# T4p1_thruhole.net
KiCad netlist of a schematic drawn in EAGLE
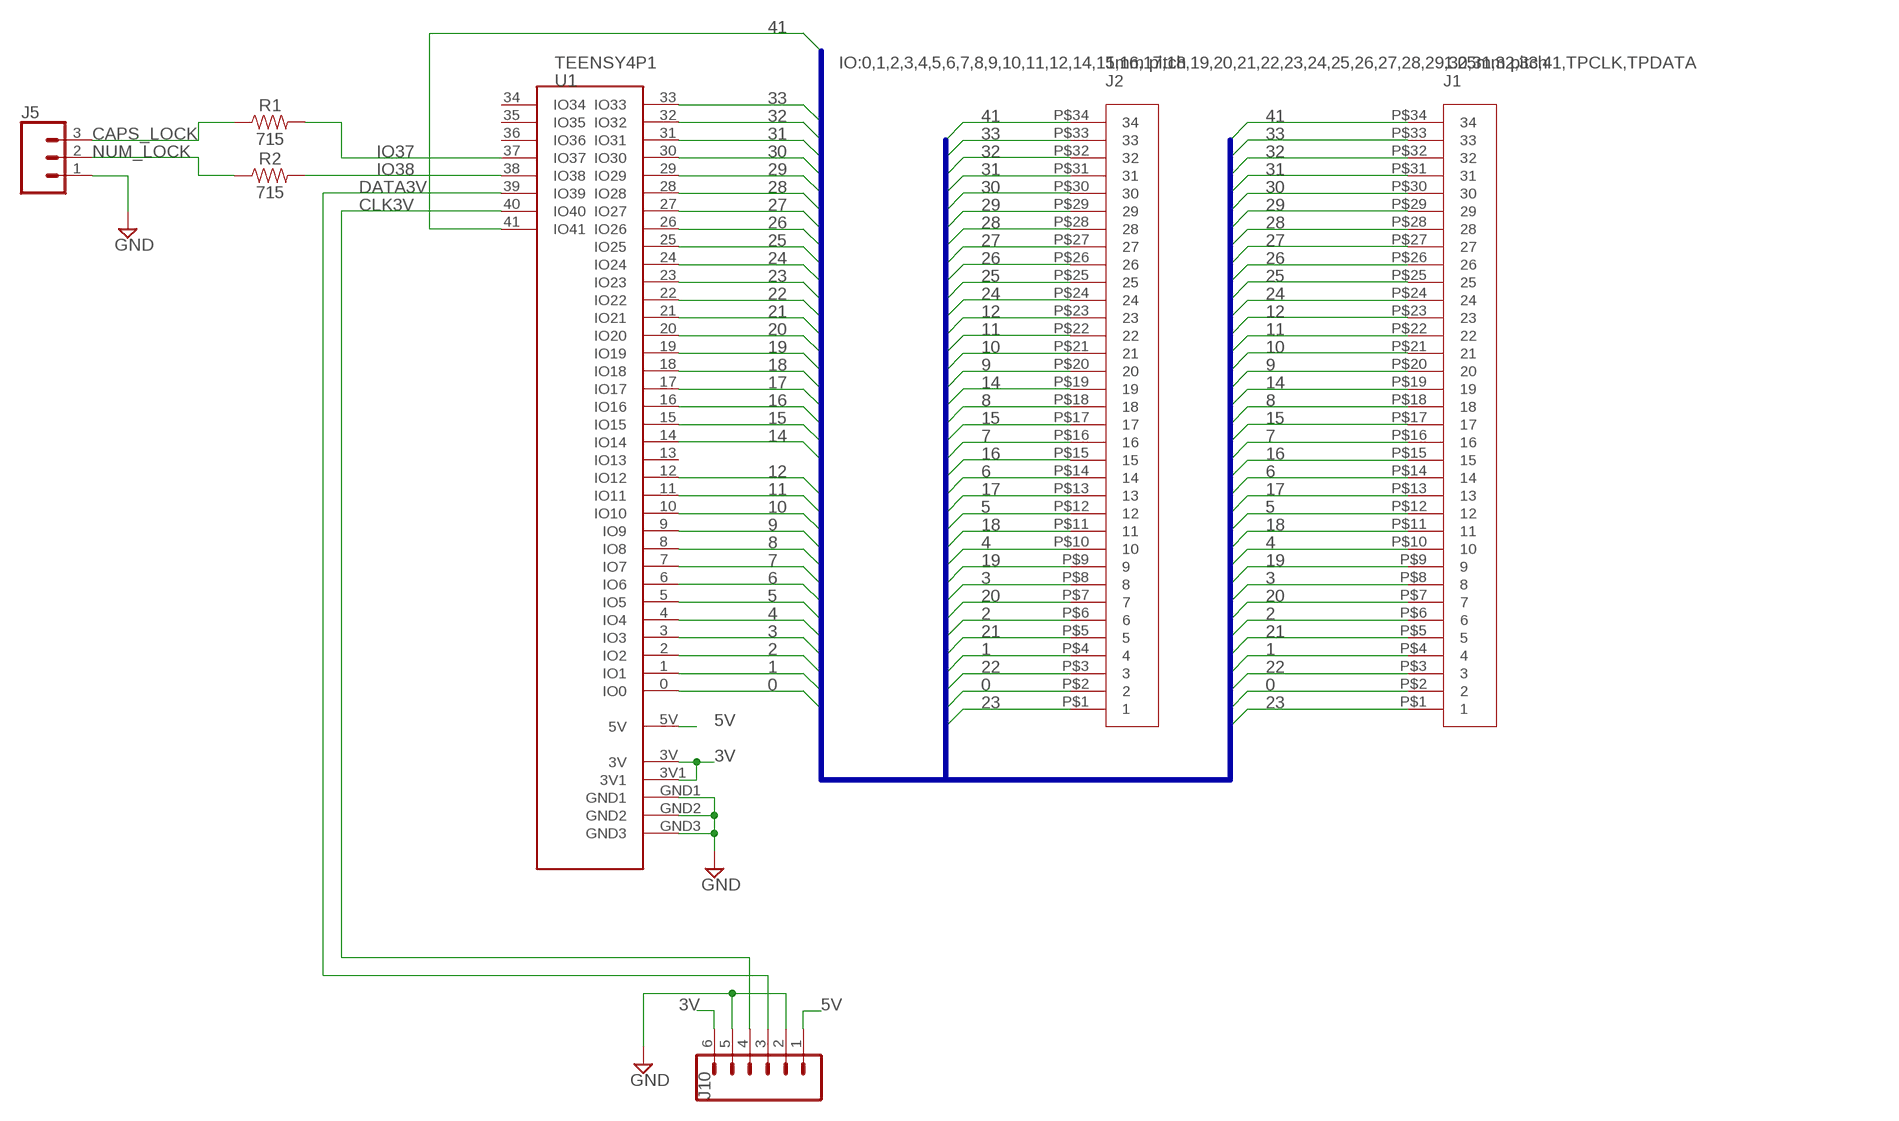
[diagram p0: schematic, sheet 1]

(export (version "E")
  (design (tool "Eeschema 10.0.6"))
  (components
    (comp (ref "J1")
      (value "1P25MM_THRUHOLE")
      (footprint "eagle-import:1P25MM_THRUHOLE")
      (libsource (lib "eagle-import") (part "1P25MM_THRUHOLE"))
    )
    (comp (ref "J2")
      (value "1MM_THRUHOLE")
      (footprint "eagle-import:1MM_THRUHOLE")
      (libsource (lib "eagle-import") (part "1MM_THRUHOLE"))
    )
    (comp (ref "J5")
      (value "CONN_031X03_NO_SILK")
      (footprint "eagle-import:1X03_NO_SILK")
      (libsource (lib "eagle-import") (part "CONN_031X03_NO_SILK"))
    )
    (comp (ref "J10")
      (value "CONN_06NO_SILK_NO_POP")
      (footprint "eagle-import:1X06_NO_SILK")
      (libsource (lib "eagle-import") (part "CONN_06NO_SILK_NO_POP"))
    )
    (comp (ref "R1")
      (value "715")
      (footprint "eagle-import:AXIAL-0.3")
      (libsource (lib "eagle-import") (part "RESISTOR_AXIAL"))
    )
    (comp (ref "R2")
      (value "715")
      (footprint "eagle-import:AXIAL-0.3")
      (libsource (lib "eagle-import") (part "RESISTOR_AXIAL"))
    )
    (comp (ref "U1")
      (value "TEENSY4P1")
      (footprint "eagle-import:TEENSY4P1")
      (libsource (lib "eagle-import") (part "TEENSYP41"))
    )
  )
  (nets
    (net (code "4") (name "/0") (class "Default")
      (node (ref "J1") (pin "P$2") (pinfunction "2_P$2") (pintype "bidirectional"))
      (node (ref "J2") (pin "P$2") (pinfunction "2_P$2") (pintype "bidirectional"))
      (node (ref "U1") (pin "0") (pinfunction "IO0_0") (pintype "bidirectional"))
    )
    (net (code "5") (name "/1") (class "Default")
      (node (ref "J1") (pin "P$4") (pinfunction "4_P$4") (pintype "bidirectional"))
      (node (ref "J2") (pin "P$4") (pinfunction "4_P$4") (pintype "bidirectional"))
      (node (ref "U1") (pin "1") (pinfunction "IO1_1") (pintype "bidirectional"))
    )
    (net (code "6") (name "/2") (class "Default")
      (node (ref "J1") (pin "P$6") (pinfunction "6_P$6") (pintype "bidirectional"))
      (node (ref "J2") (pin "P$6") (pinfunction "6_P$6") (pintype "bidirectional"))
      (node (ref "U1") (pin "2") (pinfunction "IO2_2") (pintype "bidirectional"))
    )
    (net (code "7") (name "/3") (class "Default")
      (node (ref "J1") (pin "P$8") (pinfunction "8_P$8") (pintype "bidirectional"))
      (node (ref "J2") (pin "P$8") (pinfunction "8_P$8") (pintype "bidirectional"))
      (node (ref "U1") (pin "3") (pinfunction "IO3_3") (pintype "bidirectional"))
    )
    (net (code "8") (name "/3V") (class "Default")
      (node (ref "J10") (pin "6") (pinfunction "6_6") (pintype "passive"))
      (node (ref "U1") (pin "3V") (pinfunction "3V_3V") (pintype "bidirectional"))
      (node (ref "U1") (pin "3V1") (pinfunction "3V1_3V1") (pintype "bidirectional"))
    )
    (net (code "9") (name "/4") (class "Default")
      (node (ref "J1") (pin "P$10") (pinfunction "10_P$10") (pintype "bidirectional"))
      (node (ref "J2") (pin "P$10") (pinfunction "10_P$10") (pintype "bidirectional"))
      (node (ref "U1") (pin "4") (pinfunction "IO4_4") (pintype "bidirectional"))
    )
    (net (code "10") (name "/5") (class "Default")
      (node (ref "J1") (pin "P$12") (pinfunction "12_P$12") (pintype "bidirectional"))
      (node (ref "J2") (pin "P$12") (pinfunction "12_P$12") (pintype "bidirectional"))
      (node (ref "U1") (pin "5") (pinfunction "IO5_5") (pintype "bidirectional"))
    )
    (net (code "11") (name "/5V") (class "Default")
      (node (ref "J10") (pin "1") (pinfunction "1_1") (pintype "passive"))
      (node (ref "U1") (pin "5V") (pinfunction "5V_5V") (pintype "bidirectional"))
    )
    (net (code "12") (name "/6") (class "Default")
      (node (ref "J1") (pin "P$14") (pinfunction "14_P$14") (pintype "bidirectional"))
      (node (ref "J2") (pin "P$14") (pinfunction "14_P$14") (pintype "bidirectional"))
      (node (ref "U1") (pin "6") (pinfunction "IO6_6") (pintype "bidirectional"))
    )
    (net (code "13") (name "/7") (class "Default")
      (node (ref "J1") (pin "P$16") (pinfunction "16_P$16") (pintype "bidirectional"))
      (node (ref "J2") (pin "P$16") (pinfunction "16_P$16") (pintype "bidirectional"))
      (node (ref "U1") (pin "7") (pinfunction "IO7_7") (pintype "bidirectional"))
    )
    (net (code "14") (name "/8") (class "Default")
      (node (ref "J1") (pin "P$18") (pinfunction "18_P$18") (pintype "bidirectional"))
      (node (ref "J2") (pin "P$18") (pinfunction "18_P$18") (pintype "bidirectional"))
      (node (ref "U1") (pin "8") (pinfunction "IO8_8") (pintype "bidirectional"))
    )
    (net (code "15") (name "/9") (class "Default")
      (node (ref "J1") (pin "P$20") (pinfunction "20_P$20") (pintype "bidirectional"))
      (node (ref "J2") (pin "P$20") (pinfunction "20_P$20") (pintype "bidirectional"))
      (node (ref "U1") (pin "9") (pinfunction "IO9_9") (pintype "bidirectional"))
    )
    (net (code "16") (name "/10") (class "Default")
      (node (ref "J1") (pin "P$21") (pinfunction "21_P$21") (pintype "bidirectional"))
      (node (ref "J2") (pin "P$21") (pinfunction "21_P$21") (pintype "bidirectional"))
      (node (ref "U1") (pin "10") (pinfunction "IO10_10") (pintype "bidirectional"))
    )
    (net (code "17") (name "/11") (class "Default")
      (node (ref "J1") (pin "P$22") (pinfunction "22_P$22") (pintype "bidirectional"))
      (node (ref "J2") (pin "P$22") (pinfunction "22_P$22") (pintype "bidirectional"))
      (node (ref "U1") (pin "11") (pinfunction "IO11_11") (pintype "bidirectional"))
    )
    (net (code "18") (name "/12") (class "Default")
      (node (ref "J1") (pin "P$23") (pinfunction "23_P$23") (pintype "bidirectional"))
      (node (ref "J2") (pin "P$23") (pinfunction "23_P$23") (pintype "bidirectional"))
      (node (ref "U1") (pin "12") (pinfunction "IO12_12") (pintype "bidirectional"))
    )
    (net (code "19") (name "/14") (class "Default")
      (node (ref "J1") (pin "P$19") (pinfunction "19_P$19") (pintype "bidirectional"))
      (node (ref "J2") (pin "P$19") (pinfunction "19_P$19") (pintype "bidirectional"))
      (node (ref "U1") (pin "14") (pinfunction "IO14_14") (pintype "bidirectional"))
    )
    (net (code "20") (name "/15") (class "Default")
      (node (ref "J1") (pin "P$17") (pinfunction "17_P$17") (pintype "bidirectional"))
      (node (ref "J2") (pin "P$17") (pinfunction "17_P$17") (pintype "bidirectional"))
      (node (ref "U1") (pin "15") (pinfunction "IO15_15") (pintype "bidirectional"))
    )
    (net (code "21") (name "/16") (class "Default")
      (node (ref "J1") (pin "P$15") (pinfunction "15_P$15") (pintype "bidirectional"))
      (node (ref "J2") (pin "P$15") (pinfunction "15_P$15") (pintype "bidirectional"))
      (node (ref "U1") (pin "16") (pinfunction "IO16_16") (pintype "bidirectional"))
    )
    (net (code "22") (name "/17") (class "Default")
      (node (ref "J1") (pin "P$13") (pinfunction "13_P$13") (pintype "bidirectional"))
      (node (ref "J2") (pin "P$13") (pinfunction "13_P$13") (pintype "bidirectional"))
      (node (ref "U1") (pin "17") (pinfunction "IO17_17") (pintype "bidirectional"))
    )
    (net (code "23") (name "/18") (class "Default")
      (node (ref "J1") (pin "P$11") (pinfunction "11_P$11") (pintype "bidirectional"))
      (node (ref "J2") (pin "P$11") (pinfunction "11_P$11") (pintype "bidirectional"))
      (node (ref "U1") (pin "18") (pinfunction "IO18_18") (pintype "bidirectional"))
    )
    (net (code "24") (name "/19") (class "Default")
      (node (ref "J1") (pin "P$9") (pinfunction "9_P$9") (pintype "bidirectional"))
      (node (ref "J2") (pin "P$9") (pinfunction "9_P$9") (pintype "bidirectional"))
      (node (ref "U1") (pin "19") (pinfunction "IO19_19") (pintype "bidirectional"))
    )
    (net (code "25") (name "/20") (class "Default")
      (node (ref "J1") (pin "P$7") (pinfunction "7_P$7") (pintype "bidirectional"))
      (node (ref "J2") (pin "P$7") (pinfunction "7_P$7") (pintype "bidirectional"))
      (node (ref "U1") (pin "20") (pinfunction "IO20_20") (pintype "bidirectional"))
    )
    (net (code "26") (name "/21") (class "Default")
      (node (ref "J1") (pin "P$5") (pinfunction "5_P$5") (pintype "bidirectional"))
      (node (ref "J2") (pin "P$5") (pinfunction "5_P$5") (pintype "bidirectional"))
      (node (ref "U1") (pin "21") (pinfunction "IO21_21") (pintype "bidirectional"))
    )
    (net (code "27") (name "/22") (class "Default")
      (node (ref "J1") (pin "P$3") (pinfunction "3_P$3") (pintype "bidirectional"))
      (node (ref "J2") (pin "P$3") (pinfunction "3_P$3") (pintype "bidirectional"))
      (node (ref "U1") (pin "22") (pinfunction "IO22_22") (pintype "bidirectional"))
    )
    (net (code "28") (name "/23") (class "Default")
      (node (ref "J1") (pin "P$1") (pinfunction "1_P$1") (pintype "bidirectional"))
      (node (ref "J2") (pin "P$1") (pinfunction "1_P$1") (pintype "bidirectional"))
      (node (ref "U1") (pin "23") (pinfunction "IO23_23") (pintype "bidirectional"))
    )
    (net (code "29") (name "/24") (class "Default")
      (node (ref "J1") (pin "P$24") (pinfunction "24_P$24") (pintype "bidirectional"))
      (node (ref "J2") (pin "P$24") (pinfunction "24_P$24") (pintype "bidirectional"))
      (node (ref "U1") (pin "24") (pinfunction "IO24_24") (pintype "bidirectional"))
    )
    (net (code "30") (name "/25") (class "Default")
      (node (ref "J1") (pin "P$25") (pinfunction "25_P$25") (pintype "bidirectional"))
      (node (ref "J2") (pin "P$25") (pinfunction "25_P$25") (pintype "bidirectional"))
      (node (ref "U1") (pin "25") (pinfunction "IO25_25") (pintype "bidirectional"))
    )
    (net (code "31") (name "/26") (class "Default")
      (node (ref "J1") (pin "P$26") (pinfunction "26_P$26") (pintype "bidirectional"))
      (node (ref "J2") (pin "P$26") (pinfunction "26_P$26") (pintype "bidirectional"))
      (node (ref "U1") (pin "26") (pinfunction "IO26_26") (pintype "bidirectional"))
    )
    (net (code "32") (name "/27") (class "Default")
      (node (ref "J1") (pin "P$27") (pinfunction "27_P$27") (pintype "bidirectional"))
      (node (ref "J2") (pin "P$27") (pinfunction "27_P$27") (pintype "bidirectional"))
      (node (ref "U1") (pin "27") (pinfunction "IO27_27") (pintype "bidirectional"))
    )
    (net (code "33") (name "/28") (class "Default")
      (node (ref "J1") (pin "P$28") (pinfunction "28_P$28") (pintype "bidirectional"))
      (node (ref "J2") (pin "P$28") (pinfunction "28_P$28") (pintype "bidirectional"))
      (node (ref "U1") (pin "28") (pinfunction "IO28_28") (pintype "bidirectional"))
    )
    (net (code "34") (name "/29") (class "Default")
      (node (ref "J1") (pin "P$29") (pinfunction "29_P$29") (pintype "bidirectional"))
      (node (ref "J2") (pin "P$29") (pinfunction "29_P$29") (pintype "bidirectional"))
      (node (ref "U1") (pin "29") (pinfunction "IO29_29") (pintype "bidirectional"))
    )
    (net (code "35") (name "/30") (class "Default")
      (node (ref "J1") (pin "P$30") (pinfunction "30_P$30") (pintype "bidirectional"))
      (node (ref "J2") (pin "P$30") (pinfunction "30_P$30") (pintype "bidirectional"))
      (node (ref "U1") (pin "30") (pinfunction "IO30_30") (pintype "bidirectional"))
    )
    (net (code "36") (name "/31") (class "Default")
      (node (ref "J1") (pin "P$31") (pinfunction "31_P$31") (pintype "bidirectional"))
      (node (ref "J2") (pin "P$31") (pinfunction "31_P$31") (pintype "bidirectional"))
      (node (ref "U1") (pin "31") (pinfunction "IO31_31") (pintype "bidirectional"))
    )
    (net (code "37") (name "/32") (class "Default")
      (node (ref "J1") (pin "P$32") (pinfunction "32_P$32") (pintype "bidirectional"))
      (node (ref "J2") (pin "P$32") (pinfunction "32_P$32") (pintype "bidirectional"))
      (node (ref "U1") (pin "32") (pinfunction "IO32_32") (pintype "bidirectional"))
    )
    (net (code "38") (name "/33") (class "Default")
      (node (ref "J1") (pin "P$33") (pinfunction "33_P$33") (pintype "bidirectional"))
      (node (ref "J2") (pin "P$33") (pinfunction "33_P$33") (pintype "bidirectional"))
      (node (ref "U1") (pin "33") (pinfunction "IO33_33") (pintype "bidirectional"))
    )
    (net (code "39") (name "/41") (class "Default")
      (node (ref "J1") (pin "P$34") (pinfunction "34_P$34") (pintype "bidirectional"))
      (node (ref "J2") (pin "P$34") (pinfunction "34_P$34") (pintype "bidirectional"))
      (node (ref "U1") (pin "41") (pinfunction "IO41_41") (pintype "bidirectional"))
    )
    (net (code "40") (name "/CAPS_LOCK") (class "Default")
      (node (ref "J5") (pin "3") (pinfunction "3_3") (pintype "passive"))
      (node (ref "R1") (pin "P$1") (pinfunction "1_P$1") (pintype "passive"))
    )
    (net (code "41") (name "/CLK3V") (class "Default")
      (node (ref "J10") (pin "4") (pinfunction "4_4") (pintype "passive"))
      (node (ref "U1") (pin "40") (pinfunction "IO40_40") (pintype "bidirectional"))
    )
    (net (code "42") (name "/DATA3V") (class "Default")
      (node (ref "J10") (pin "3") (pinfunction "3_3") (pintype "passive"))
      (node (ref "U1") (pin "39") (pinfunction "IO39_39") (pintype "bidirectional"))
    )
    (net (code "43") (name "/IO37") (class "Default")
      (node (ref "R1") (pin "P$2") (pinfunction "2_P$2") (pintype "passive"))
      (node (ref "U1") (pin "37") (pinfunction "IO37_37") (pintype "bidirectional"))
    )
    (net (code "44") (name "/IO38") (class "Default")
      (node (ref "R2") (pin "P$2") (pinfunction "2_P$2") (pintype "passive"))
      (node (ref "U1") (pin "38") (pinfunction "IO38_38") (pintype "bidirectional"))
    )
    (net (code "45") (name "/NUM_LOCK") (class "Default")
      (node (ref "J5") (pin "2") (pinfunction "2_2") (pintype "passive"))
      (node (ref "R2") (pin "P$1") (pinfunction "1_P$1") (pintype "passive"))
    )
    (net (code "47") (name "GND") (class "Default")
      (node (ref "J10") (pin "2") (pinfunction "2_2") (pintype "passive"))
      (node (ref "J10") (pin "5") (pinfunction "5_5") (pintype "passive"))
      (node (ref "J5") (pin "1") (pinfunction "1_1") (pintype "passive"))
      (node (ref "U1") (pin "GND1") (pinfunction "GND1_GND1") (pintype "bidirectional"))
      (node (ref "U1") (pin "GND2") (pinfunction "GND2_GND2") (pintype "bidirectional"))
      (node (ref "U1") (pin "GND3") (pinfunction "GND3_GND3") (pintype "bidirectional"))
    )
    (net (code "48") (name "unconnected-(U1-IO13-Pad13)") (class "Default")
      (node (ref "U1") (pin "13") (pinfunction "IO13_13") (pintype "bidirectional"))
    )
    (net (code "49") (name "unconnected-(U1-IO34-Pad34)") (class "Default")
      (node (ref "U1") (pin "34") (pinfunction "IO34_34") (pintype "bidirectional"))
    )
    (net (code "50") (name "unconnected-(U1-IO35-Pad35)") (class "Default")
      (node (ref "U1") (pin "35") (pinfunction "IO35_35") (pintype "bidirectional"))
    )
    (net (code "51") (name "unconnected-(U1-IO36-Pad36)") (class "Default")
      (node (ref "U1") (pin "36") (pinfunction "IO36_36") (pintype "bidirectional"))
    )
  )
)
